# Sheet2.net
KiCad netlist of a schematic drawn in Altium Designer
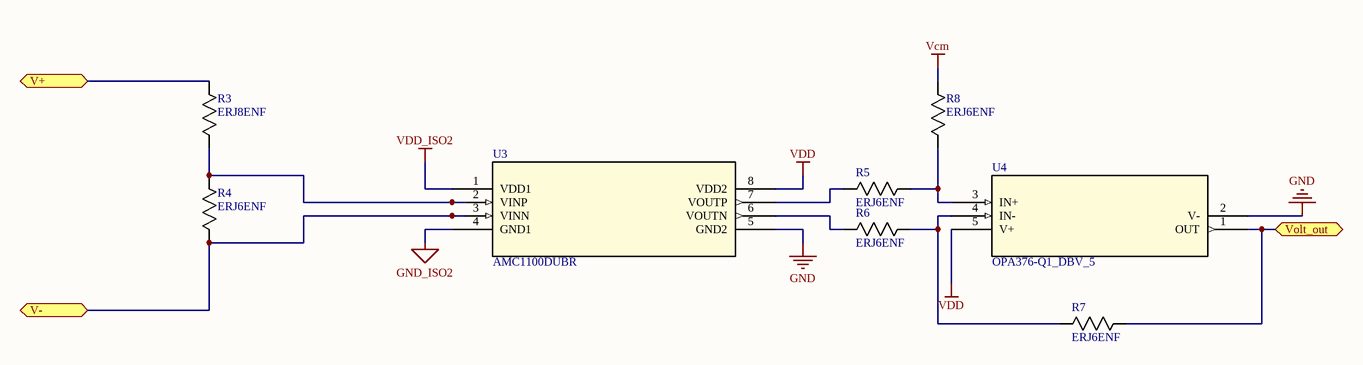
[diagram p0: Sheet2.SchDoc]

(export (version "E")
  (design (tool "Eeschema 10.0.6"))
  (components
    (comp (ref "R3")
      (value "ERJ8ENF")
      (footprint "1206")
      (description "Imported")
      (fields (field (name "MANUFACTURER_PART_NUMBER") "ERJ8ENF1000V"))
      (libsource (lib "ERJ8EN_250mW") (part "ERJ8ENF"))
    )
    (comp (ref "R4")
      (value "ERJ6ENF")
      (footprint "0805")
      (description "Imported")
      (fields (field (name "MANUFACTURER_PART_NUMBER") "ERJ6ENF1000V"))
      (libsource (lib "ERJ6EN_125mW") (part "ERJ6ENF"))
    )
    (comp (ref "R5")
      (value "ERJ6ENF")
      (footprint "0805")
      (description "Imported")
      (fields (field (name "MANUFACTURER_PART_NUMBER") "ERJ6ENF1000V"))
      (libsource (lib "ERJ6EN_125mW") (part "ERJ6ENF"))
    )
    (comp (ref "R6")
      (value "ERJ6ENF")
      (footprint "0805")
      (description "Imported")
      (fields (field (name "MANUFACTURER_PART_NUMBER") "ERJ6ENF1000V"))
      (libsource (lib "ERJ6EN_125mW") (part "ERJ6ENF"))
    )
    (comp (ref "R7")
      (value "ERJ6ENF")
      (footprint "0805")
      (description "Imported")
      (fields (field (name "MANUFACTURER_PART_NUMBER") "ERJ6ENF1000V"))
      (libsource (lib "ERJ6EN_125mW") (part "ERJ6ENF"))
    )
    (comp (ref "R8")
      (value "ERJ6ENF")
      (footprint "0805")
      (description "Imported")
      (fields (field (name "MANUFACTURER_PART_NUMBER") "ERJ6ENF1000V"))
      (libsource (lib "ERJ6EN_125mW") (part "ERJ6ENF"))
    )
    (comp (ref "U3")
      (value "AMC1100DUBR")
      (footprint "DUB8")
      (description "Imported")
      (libsource (lib "AltiumDesigner") (part "AMC1100DUBR"))
    )
    (comp (ref "U4")
      (value "OPA376-Q1_DBV_5")
      (footprint "DBV5")
      (description "Imported")
      (fields (field (name "MANUFACTURER") "Texas Instruments"))
      (libsource (lib "OPA376") (part "OPA376-Q1_DBV_5"))
    )
  )
  (nets
    (net (code "1") (name "/V+") (class "Default")
      (node (ref "R3") (pin "2") (pinfunction "2_2") (pintype "passive"))
    )
    (net (code "2") (name "/V-") (class "Default")
      (node (ref "R4") (pin "1") (pinfunction "1_1") (pintype "passive"))
      (node (ref "U3") (pin "3") (pinfunction "VINN_3") (pintype "input"))
    )
    (net (code "3") (name "/Volt_out") (class "Default")
      (node (ref "R7") (pin "2") (pinfunction "2_2") (pintype "passive"))
      (node (ref "U4") (pin "1") (pinfunction "OUT_1") (pintype "output"))
    )
    (net (code "4") (name "GND") (class "Default")
      (node (ref "U3") (pin "5") (pinfunction "GND2_5") (pintype "power_in"))
      (node (ref "U4") (pin "2") (pinfunction "V-_2") (pintype "power_in"))
    )
    (net (code "5") (name "GND_ISO2") (class "Default")
      (node (ref "U3") (pin "4") (pinfunction "GND1_4") (pintype "power_in"))
    )
    (net (code "6") (name "Net-(U3-VINP)") (class "Default")
      (node (ref "R3") (pin "1") (pinfunction "1_1") (pintype "passive"))
      (node (ref "R4") (pin "2") (pinfunction "2_2") (pintype "passive"))
      (node (ref "U3") (pin "2") (pinfunction "VINP_2") (pintype "input"))
    )
    (net (code "7") (name "Net-(U3-VOUTN)") (class "Default")
      (node (ref "R6") (pin "1") (pinfunction "1_1") (pintype "passive"))
      (node (ref "U3") (pin "6") (pinfunction "VOUTN_6") (pintype "output"))
    )
    (net (code "8") (name "Net-(U3-VOUTP)") (class "Default")
      (node (ref "R5") (pin "1") (pinfunction "1_1") (pintype "passive"))
      (node (ref "U3") (pin "7") (pinfunction "VOUTP_7") (pintype "output"))
    )
    (net (code "9") (name "Net-(U4-IN+)") (class "Default")
      (node (ref "R5") (pin "2") (pinfunction "2_2") (pintype "passive"))
      (node (ref "R8") (pin "1") (pinfunction "1_1") (pintype "passive"))
      (node (ref "U4") (pin "3") (pinfunction "IN+_3") (pintype "input"))
    )
    (net (code "10") (name "Net-(U4-IN-)") (class "Default")
      (node (ref "R6") (pin "2") (pinfunction "2_2") (pintype "passive"))
      (node (ref "R7") (pin "1") (pinfunction "1_1") (pintype "passive"))
      (node (ref "U4") (pin "4") (pinfunction "IN-_4") (pintype "input"))
    )
    (net (code "11") (name "VDD") (class "Default")
      (node (ref "U3") (pin "8") (pinfunction "VDD2_8") (pintype "power_in"))
      (node (ref "U4") (pin "5") (pinfunction "V+_5") (pintype "power_in"))
    )
    (net (code "12") (name "VDD_ISO2") (class "Default")
      (node (ref "U3") (pin "1") (pinfunction "VDD1_1") (pintype "power_in"))
    )
    (net (code "13") (name "Vcm") (class "Default")
      (node (ref "R8") (pin "2") (pinfunction "2_2") (pintype "passive"))
    )
  )
)
